# FET-module.net
KiCad netlist of a schematic drawn in Altium Designer
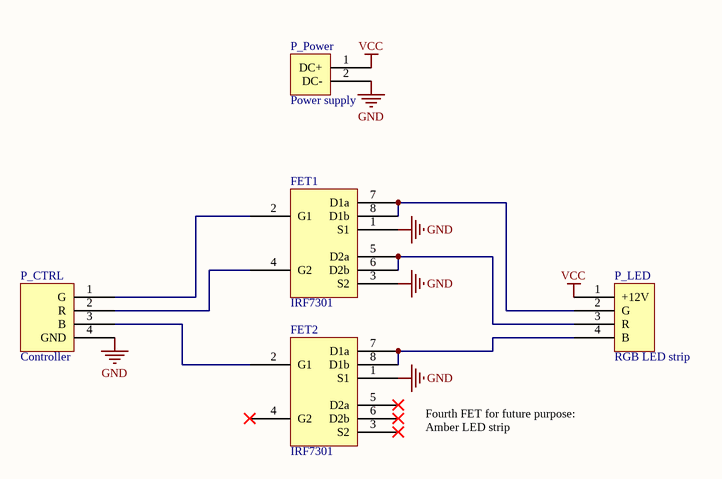
[diagram p0: FET-module.SchDoc]

(export (version "E")
  (design (tool "Eeschema 10.0.6"))
  (components
    (comp (ref "FET1")
      (value "IRF7301")
      (footprint "SOIC8 - IRF FET")
      (libsource (lib "FET-module") (part "IRF7301"))
    )
    (comp (ref "FET2")
      (value "IRF7301")
      (footprint "SOIC8 - IRF FET")
      (libsource (lib "FET-module") (part "IRF7301"))
    )
    (comp (ref "P_CTRL")
      (value "Controller")
      (footprint "Controller connector")
      (libsource (lib "FET-module") (part "Controller"))
    )
    (comp (ref "P_LED")
      (value "RGB LED strip")
      (footprint "LED strip RGB connector")
      (libsource (lib "FET-module") (part "RGB LED strip"))
    )
    (comp (ref "P_Power")
      (value "Power supply")
      (footprint "DC connector")
      (libsource (lib "FET-module") (part "Power supply"))
    )
  )
  (nets
    (net (code "1") (name "GND") (class "Default")
      (node (ref "FET1") (pin "1") (pinfunction "S1_1") (pintype "passive"))
      (node (ref "FET1") (pin "3") (pinfunction "S2_3") (pintype "passive"))
      (node (ref "FET2") (pin "1") (pinfunction "S1_1") (pintype "passive"))
      (node (ref "P_CTRL") (pin "4") (pinfunction "GND_4") (pintype "passive"))
      (node (ref "P_Power") (pin "2") (pinfunction "DC-_2") (pintype "passive"))
    )
    (net (code "2") (name "Net-(FET1-D1a)") (class "Default")
      (node (ref "FET1") (pin "7") (pinfunction "D1a_7") (pintype "passive"))
      (node (ref "FET1") (pin "8") (pinfunction "D1b_8") (pintype "passive"))
      (node (ref "P_LED") (pin "2") (pinfunction "G_2") (pintype "passive"))
    )
    (net (code "3") (name "Net-(FET1-D2a)") (class "Default")
      (node (ref "FET1") (pin "5") (pinfunction "D2a_5") (pintype "passive"))
      (node (ref "FET1") (pin "6") (pinfunction "D2b_6") (pintype "passive"))
      (node (ref "P_LED") (pin "3") (pinfunction "R_3") (pintype "passive"))
    )
    (net (code "4") (name "Net-(FET1-G1)") (class "Default")
      (node (ref "FET1") (pin "2") (pinfunction "G1_2") (pintype "passive"))
      (node (ref "P_CTRL") (pin "1") (pinfunction "G_1") (pintype "passive"))
    )
    (net (code "5") (name "Net-(FET1-G2)") (class "Default")
      (node (ref "FET1") (pin "4") (pinfunction "G2_4") (pintype "passive"))
      (node (ref "P_CTRL") (pin "2") (pinfunction "R_2") (pintype "passive"))
    )
    (net (code "6") (name "Net-(FET2-D1a)") (class "Default")
      (node (ref "FET2") (pin "7") (pinfunction "D1a_7") (pintype "passive"))
      (node (ref "FET2") (pin "8") (pinfunction "D1b_8") (pintype "passive"))
      (node (ref "P_LED") (pin "4") (pinfunction "B_4") (pintype "passive"))
    )
    (net (code "7") (name "Net-(FET2-G1)") (class "Default")
      (node (ref "FET2") (pin "2") (pinfunction "G1_2") (pintype "passive"))
      (node (ref "P_CTRL") (pin "3") (pinfunction "B_3") (pintype "passive"))
    )
    (net (code "8") (name "VCC") (class "Default")
      (node (ref "P_LED") (pin "1") (pinfunction "+12V_1") (pintype "passive"))
      (node (ref "P_Power") (pin "1") (pinfunction "DC+_1") (pintype "passive"))
    )
    (net (code "9") (name "unconnected-(FET2-D2a-Pad5)") (class "Default")
      (node (ref "FET2") (pin "5") (pinfunction "D2a_5") (pintype "passive+no_connect"))
    )
    (net (code "10") (name "unconnected-(FET2-D2b-Pad6)") (class "Default")
      (node (ref "FET2") (pin "6") (pinfunction "D2b_6") (pintype "passive+no_connect"))
    )
    (net (code "11") (name "unconnected-(FET2-G2-Pad4)") (class "Default")
      (node (ref "FET2") (pin "4") (pinfunction "G2_4") (pintype "passive+no_connect"))
    )
    (net (code "12") (name "unconnected-(FET2-S2-Pad3)") (class "Default")
      (node (ref "FET2") (pin "3") (pinfunction "S2_3") (pintype "passive+no_connect"))
    )
  )
)
